# Atmega328.net
KiCad netlist of a schematic drawn in Altium Designer
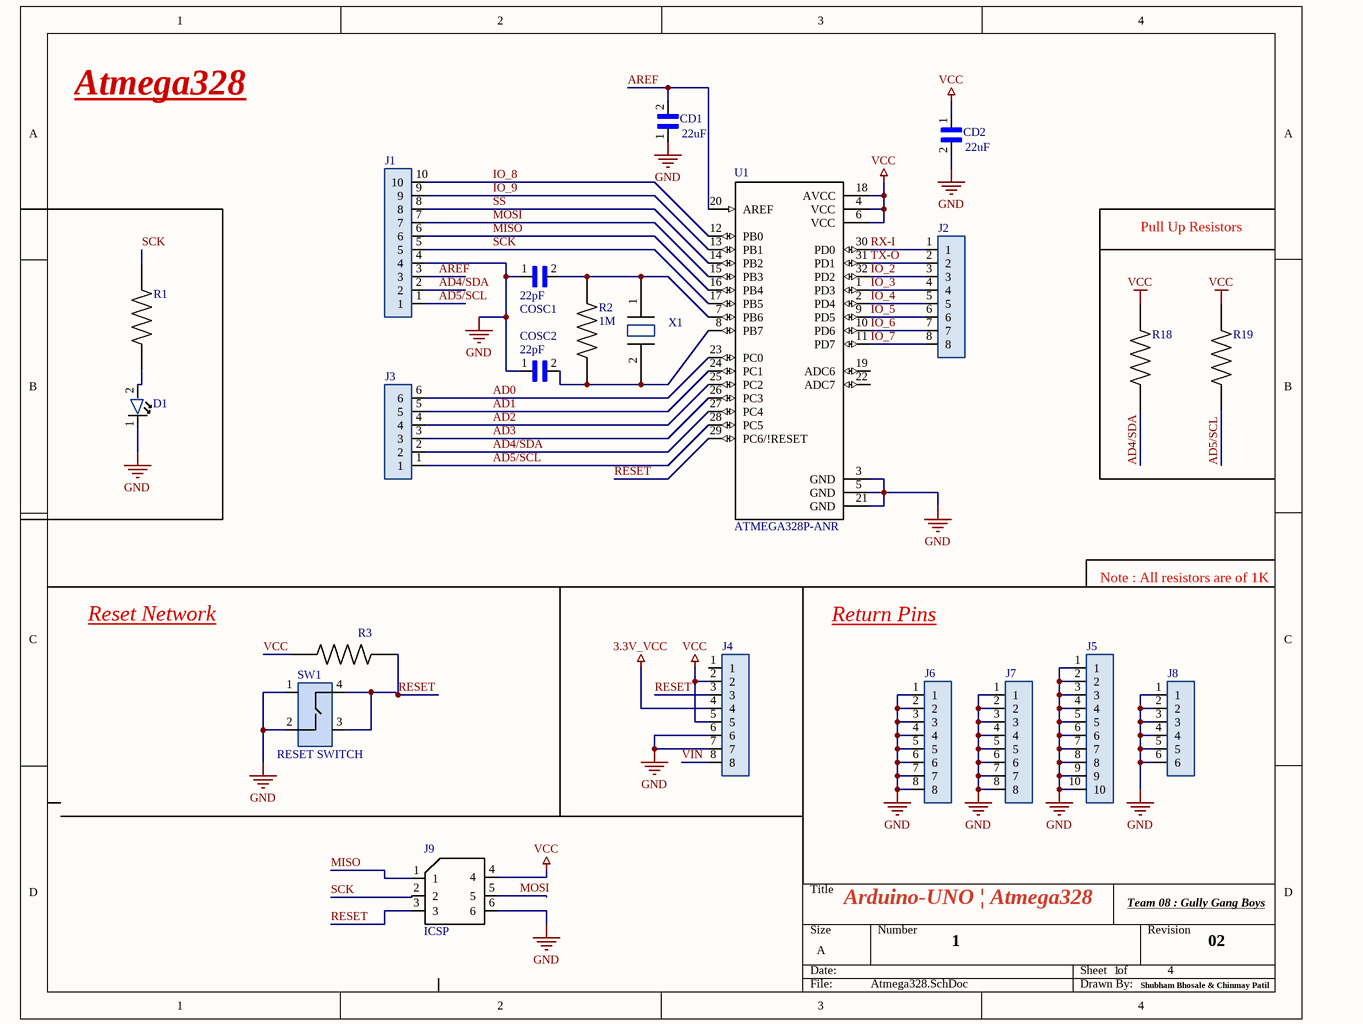
[diagram p0: Atmega328.SchDoc]

(export (version "E")
  (design (tool "Eeschema 10.0.6"))
  (components
    (comp (ref "CD1")
      (value "22uF")
      (footprint "1206_Passive")
      (description "22µF ±20% 16V Ceramic Capacitor X5R 1206 (3216 Metric)")
      (fields (field (name "DIGIKEY PART") "1276-2728-1-ND"))
      (libsource (lib "brd2_rev2") (part "1206_22uF"))
    )
    (comp (ref "CD2")
      (value "22uF")
      (footprint "1206_Passive")
      (description "22µF ±20% 16V Ceramic Capacitor X5R 1206 (3216 Metric)")
      (fields (field (name "DIGIKEY PART") "1276-2728-1-ND"))
      (libsource (lib "brd2_rev2") (part "1206_22uF"))
    )
    (comp (ref "COSC1")
      (value "22pF")
      (footprint "1206_Passive")
      (description "22pF ±5% 16V Ceramic Capacitor C0G, NP0 1206 (3216 Metric)")
      (fields (field (name "DIGIKEY PART") "732-7867-1-ND"))
      (libsource (lib "brd2_rev2") (part "1206_22pF"))
    )
    (comp (ref "COSC2")
      (value "22pF")
      (footprint "1206_Passive")
      (description "22pF ±5% 16V Ceramic Capacitor C0G, NP0 1206 (3216 Metric)")
      (fields (field (name "DIGIKEY PART") "732-7867-1-ND"))
      (libsource (lib "brd2_rev2") (part "1206_22pF"))
    )
    (comp (ref "D1")
      (value "LTST-C150CKT")
      (footprint "LED")
      (description "Red 638nm LED Indication - Discrete 1.8V 1206 (3216 Metric)")
      (fields (field (name "DIGIKEY PART") "160-1167-1-ND"))
      (libsource (lib "brd2_rev2") (part "1206_RED_LED"))
    )
    (comp (ref "J1")
      (value "PPTC101LFBN-RC")
      (footprint "10_PIN")
      (description "10 Position Header Connector 0.100\" (2.54mm) Through Hole Tin")
      (fields (field (name "DIGIKEY PART") "S7008-ND"))
      (libsource (lib "brd2_rev2") (part "10_PIN_FEMALE"))
    )
    (comp (ref "J2")
      (value "PPTC081LFBN-RC")
      (footprint "8_PIN")
      (description "8 Position Header Connector 0.100\" (2.54mm) Through Hole Tin")
      (fields (field (name "DIGIKEY PART") "S7006-ND"))
      (libsource (lib "brd2_rev2") (part "8_PIN_FEMALE"))
    )
    (comp (ref "J3")
      (value "PPTC061LFBN-RC")
      (footprint "6_PIN")
      (description "6 Position Header Connector 0.100\" (2.54mm) Through Hole Tin")
      (fields (field (name "DIGIKEY PART") "S7004-ND"))
      (libsource (lib "") (part "6_PIN_FEMALE_1"))
    )
    (comp (ref "J4")
      (value "PPTC081LFBN-RC")
      (footprint "8_PIN")
      (description "8 Position Header Connector 0.100\" (2.54mm) Through Hole Tin")
      (fields (field (name "DIGIKEY PART") "S7006-ND"))
      (libsource (lib "brd2_rev2") (part "8_PIN_FEMALE"))
    )
    (comp (ref "J5")
      (value "PPTC101LFBN-RC")
      (footprint "10_PIN")
      (description "10 Position Header Connector 0.100\" (2.54mm) Through Hole Tin")
      (fields (field (name "DIGIKEY PART") "S7008-ND"))
      (libsource (lib "") (part "10_PIN_FEMALE_1"))
    )
    (comp (ref "J6")
      (value "PPTC081LFBN-RC")
      (footprint "8_PIN")
      (description "8 Position Header Connector 0.100\" (2.54mm) Through Hole Tin")
      (fields (field (name "DIGIKEY PART") "S7006-ND"))
      (libsource (lib "brd2_rev2") (part "8_PIN_FEMALE"))
    )
    (comp (ref "J7")
      (value "PPTC081LFBN-RC")
      (footprint "8_PIN")
      (description "8 Position Header Connector 0.100\" (2.54mm) Through Hole Tin")
      (fields (field (name "DIGIKEY PART") "S7006-ND"))
      (libsource (lib "brd2_rev2") (part "8_PIN_FEMALE"))
    )
    (comp (ref "J8")
      (value "PPTC061LFBN-RC")
      (footprint "6_PIN")
      (description "6 Position Header Connector 0.100\" (2.54mm) Through Hole Tin")
      (fields (field (name "DIGIKEY PART") "S7004-ND"))
      (libsource (lib "brd2_rev2") (part "6_PIN_FEMALE"))
    )
    (comp (ref "J9")
      (value "ICSP")
      (footprint "ICSP")
      (description "Connector Header Through Hole 6 position 0.079\" (2.00mm)")
      (fields (field (name "DIGIKEY PART") "S5801-03-ND"))
      (libsource (lib "brd2_rev2") (part "ICSP"))
    )
    (comp (ref "R1")
      (value "RNCP1206FTD1K00")
      (footprint "1206_Passive")
      (description "1 kOhms ±1% 0.5W, 1/2W Chip Resistor 1206 (3216 Metric) Anti-Sulfur, Moisture Resistant Thin Film")
      (fields (field (name "DIGIKEY PART") "RNCP1206FTD1K00CT-ND"))
      (libsource (lib "brd2_rev2") (part "1206_1K"))
    )
    (comp (ref "R2")
      (value "1M")
      (footprint "1206_Passive")
      (description "1 MOhms ±5% 0.25W, 1/4W Chip Resistor 1206 (3216 Metric) Automotive AEC-Q200 Thick Film")
      (fields (field (name "DIGIKEY PART") "Number RMCF1206JT1M00CT-ND"))
      (libsource (lib "brd2_rev2") (part "1206_1M"))
    )
    (comp (ref "R3")
      (value "RNCP1206FTD1K00")
      (footprint "1206_Passive")
      (description "1 kOhms ±1% 0.5W, 1/2W Chip Resistor 1206 (3216 Metric) Anti-Sulfur, Moisture Resistant Thin Film")
      (fields (field (name "DIGIKEY PART") "RNCP1206FTD1K00CT-ND"))
      (libsource (lib "brd2_rev2") (part "1206_1K"))
    )
    (comp (ref "R18")
      (value "RNCP1206FTD1K00")
      (footprint "1206_Passive")
      (description "1 kOhms ±1% 0.5W, 1/2W Chip Resistor 1206 (3216 Metric) Anti-Sulfur, Moisture Resistant Thin Film")
      (fields (field (name "DIGIKEY PART") "RNCP1206FTD1K00CT-ND"))
      (libsource (lib "brd2_rev2") (part "1206_1K"))
    )
    (comp (ref "R19")
      (value "RNCP1206FTD1K00")
      (footprint "1206_Passive")
      (description "1 kOhms ±1% 0.5W, 1/2W Chip Resistor 1206 (3216 Metric) Anti-Sulfur, Moisture Resistant Thin Film")
      (fields (field (name "DIGIKEY PART") "RNCP1206FTD1K00CT-ND"))
      (libsource (lib "brd2_rev2") (part "1206_1K"))
    )
    (comp (ref "SW1")
      (value "RESET SWITCH")
      (footprint "Switch")
      (description "Tactile Switch SPST-NO Top Actuated Surface Mount")
      (fields (field (name "DIGIKEY PART") "EG5350CT-ND"))
      (libsource (lib "brd2_rev2") (part "Push_Button"))
    )
    (comp (ref "U1")
      (value "ATMEGA328P-ANR")
      (footprint "ATMega328P")
      (description "AVR AVR® ATmega Microcontroller IC 8-Bit 20MHz 32KB (16K x 16) FLASH 32-TQFP (7x7)")
      (fields (field (name "DIGIKEY PART") "ATMEGA328P-ANRCT-ND"))
      (libsource (lib "brd2_rev2") (part "ATMega328P"))
    )
    (comp (ref "X1")
      (value "ABLS-16.000MHZ-B4-T")
      (footprint "Crystal")
      (description "16MHz ±30ppm Crystal 18pF 40 Ohms HC-49/US")
      (fields (field (name "DIGIKEY PART") "535-10226-1-ND"))
      (libsource (lib "brd2_rev2") (part "16MHz_Crystal"))
    )
  )
  (nets
    (net (code "1") (name "/AD0") (class "Default")
      (node (ref "J3") (pin "6") (pinfunction "6_6") (pintype "passive"))
      (node (ref "U1") (pin "23") (pinfunction "PC0_23") (pintype "bidirectional"))
    )
    (net (code "2") (name "/AD1") (class "Default")
      (node (ref "J3") (pin "5") (pinfunction "5_5") (pintype "passive"))
      (node (ref "U1") (pin "24") (pinfunction "PC1_24") (pintype "bidirectional"))
    )
    (net (code "3") (name "/AD2") (class "Default")
      (node (ref "J3") (pin "4") (pinfunction "4_4") (pintype "passive"))
      (node (ref "U1") (pin "25") (pinfunction "PC2_25") (pintype "bidirectional"))
    )
    (net (code "4") (name "/AD3") (class "Default")
      (node (ref "J3") (pin "3") (pinfunction "3_3") (pintype "passive"))
      (node (ref "U1") (pin "26") (pinfunction "PC3_26") (pintype "bidirectional"))
    )
    (net (code "5") (name "/AD4{slash}SDA") (class "Default")
      (node (ref "J1") (pin "2") (pinfunction "2_2") (pintype "passive"))
      (node (ref "J3") (pin "2") (pinfunction "2_2") (pintype "passive"))
      (node (ref "R18") (pin "1") (pinfunction "1_1") (pintype "passive"))
      (node (ref "U1") (pin "27") (pinfunction "PC4_27") (pintype "bidirectional"))
    )
    (net (code "6") (name "/AD5{slash}SCL") (class "Default")
      (node (ref "J1") (pin "1") (pinfunction "1_1") (pintype "passive"))
      (node (ref "J3") (pin "1") (pinfunction "1_1") (pintype "passive"))
      (node (ref "R19") (pin "1") (pinfunction "1_1") (pintype "passive"))
      (node (ref "U1") (pin "28") (pinfunction "PC5_28") (pintype "bidirectional"))
    )
    (net (code "7") (name "/AREF") (class "Default")
      (node (ref "CD1") (pin "2") (pinfunction "2_2") (pintype "passive"))
      (node (ref "J1") (pin "3") (pinfunction "3_3") (pintype "passive"))
      (node (ref "U1") (pin "20") (pinfunction "AREF_20") (pintype "input"))
    )
    (net (code "8") (name "/IO_2") (class "Default")
      (node (ref "J2") (pin "3") (pinfunction "3_3") (pintype "passive"))
      (node (ref "U1") (pin "32") (pinfunction "PD2_32") (pintype "bidirectional"))
    )
    (net (code "9") (name "/IO_3") (class "Default")
      (node (ref "J2") (pin "4") (pinfunction "4_4") (pintype "passive"))
      (node (ref "U1") (pin "1") (pinfunction "PD3_1") (pintype "bidirectional"))
    )
    (net (code "10") (name "/IO_4") (class "Default")
      (node (ref "J2") (pin "5") (pinfunction "5_5") (pintype "passive"))
      (node (ref "U1") (pin "2") (pinfunction "PD4_2") (pintype "bidirectional"))
    )
    (net (code "11") (name "/IO_5") (class "Default")
      (node (ref "J2") (pin "6") (pinfunction "6_6") (pintype "passive"))
      (node (ref "U1") (pin "9") (pinfunction "PD5_9") (pintype "bidirectional"))
    )
    (net (code "12") (name "/IO_6") (class "Default")
      (node (ref "J2") (pin "7") (pinfunction "7_7") (pintype "passive"))
      (node (ref "U1") (pin "10") (pinfunction "PD6_10") (pintype "bidirectional"))
    )
    (net (code "13") (name "/IO_7") (class "Default")
      (node (ref "J2") (pin "8") (pinfunction "8_8") (pintype "passive"))
      (node (ref "U1") (pin "11") (pinfunction "PD7_11") (pintype "bidirectional"))
    )
    (net (code "14") (name "/IO_8") (class "Default")
      (node (ref "J1") (pin "10") (pinfunction "10_10") (pintype "passive"))
      (node (ref "U1") (pin "12") (pinfunction "PB0_12") (pintype "bidirectional"))
    )
    (net (code "15") (name "/IO_9") (class "Default")
      (node (ref "J1") (pin "9") (pinfunction "9_9") (pintype "passive"))
      (node (ref "U1") (pin "13") (pinfunction "PB1_13") (pintype "bidirectional"))
    )
    (net (code "16") (name "/MISO") (class "Default")
      (node (ref "J1") (pin "6") (pinfunction "6_6") (pintype "passive"))
      (node (ref "J9") (pin "1") (pinfunction "1_1") (pintype "passive"))
      (node (ref "U1") (pin "16") (pinfunction "PB4_16") (pintype "bidirectional"))
    )
    (net (code "17") (name "/MOSI") (class "Default")
      (node (ref "J1") (pin "7") (pinfunction "7_7") (pintype "passive"))
      (node (ref "J9") (pin "5") (pinfunction "5_5") (pintype "passive"))
      (node (ref "U1") (pin "15") (pinfunction "PB3_15") (pintype "bidirectional"))
    )
    (net (code "18") (name "/RESET") (class "Default")
      (node (ref "J4") (pin "3") (pinfunction "3_3") (pintype "passive"))
      (node (ref "J9") (pin "3") (pinfunction "3_3") (pintype "passive"))
      (node (ref "R3") (pin "2") (pinfunction "2_2") (pintype "passive"))
      (node (ref "SW1") (pin "3") (pinfunction "3_3") (pintype "passive"))
      (node (ref "SW1") (pin "4") (pinfunction "4_4") (pintype "passive"))
      (node (ref "U1") (pin "29") (pinfunction "PC6/!RESET_29") (pintype "bidirectional"))
    )
    (net (code "19") (name "/RX-I") (class "Default")
      (node (ref "J2") (pin "1") (pinfunction "1_1") (pintype "passive"))
      (node (ref "U1") (pin "30") (pinfunction "PD0_30") (pintype "bidirectional"))
    )
    (net (code "20") (name "/SCK") (class "Default")
      (node (ref "J1") (pin "5") (pinfunction "5_5") (pintype "passive"))
      (node (ref "J9") (pin "2") (pinfunction "2_2") (pintype "passive"))
      (node (ref "R1") (pin "2") (pinfunction "2_2") (pintype "passive"))
      (node (ref "U1") (pin "17") (pinfunction "PB5_17") (pintype "bidirectional"))
    )
    (net (code "21") (name "/SS") (class "Default")
      (node (ref "J1") (pin "8") (pinfunction "8_8") (pintype "passive"))
      (node (ref "U1") (pin "14") (pinfunction "PB2_14") (pintype "bidirectional"))
    )
    (net (code "22") (name "/TX-O") (class "Default")
      (node (ref "J2") (pin "2") (pinfunction "2_2") (pintype "passive"))
      (node (ref "U1") (pin "31") (pinfunction "PD1_31") (pintype "bidirectional"))
    )
    (net (code "23") (name "/VIN") (class "Default")
      (node (ref "J4") (pin "8") (pinfunction "8_8") (pintype "passive"))
    )
    (net (code "24") (name "3.3V_VCC") (class "Default")
      (node (ref "J4") (pin "4") (pinfunction "4_4") (pintype "passive"))
    )
    (net (code "25") (name "GND") (class "Default")
      (node (ref "CD1") (pin "1") (pinfunction "1_1") (pintype "passive"))
      (node (ref "CD2") (pin "2") (pinfunction "2_2") (pintype "passive"))
      (node (ref "COSC1") (pin "1") (pinfunction "1_1") (pintype "passive"))
      (node (ref "COSC2") (pin "1") (pinfunction "1_1") (pintype "passive"))
      (node (ref "D1") (pin "1") (pinfunction "1_1") (pintype "passive"))
      (node (ref "J1") (pin "4") (pinfunction "4_4") (pintype "passive"))
      (node (ref "J4") (pin "6") (pinfunction "6_6") (pintype "passive"))
      (node (ref "J4") (pin "7") (pinfunction "7_7") (pintype "passive"))
      (node (ref "J5") (pin "1") (pinfunction "1_1") (pintype "passive"))
      (node (ref "J5") (pin "10") (pinfunction "10_10") (pintype "passive"))
      (node (ref "J5") (pin "2") (pinfunction "2_2") (pintype "passive"))
      (node (ref "J5") (pin "3") (pinfunction "3_3") (pintype "passive"))
      (node (ref "J5") (pin "4") (pinfunction "4_4") (pintype "passive"))
      (node (ref "J5") (pin "5") (pinfunction "5_5") (pintype "passive"))
      (node (ref "J5") (pin "6") (pinfunction "6_6") (pintype "passive"))
      (node (ref "J5") (pin "7") (pinfunction "7_7") (pintype "passive"))
      (node (ref "J5") (pin "8") (pinfunction "8_8") (pintype "passive"))
      (node (ref "J5") (pin "9") (pinfunction "9_9") (pintype "passive"))
      (node (ref "J6") (pin "1") (pinfunction "1_1") (pintype "passive"))
      (node (ref "J6") (pin "2") (pinfunction "2_2") (pintype "passive"))
      (node (ref "J6") (pin "3") (pinfunction "3_3") (pintype "passive"))
      (node (ref "J6") (pin "4") (pinfunction "4_4") (pintype "passive"))
      (node (ref "J6") (pin "5") (pinfunction "5_5") (pintype "passive"))
      (node (ref "J6") (pin "6") (pinfunction "6_6") (pintype "passive"))
      (node (ref "J6") (pin "7") (pinfunction "7_7") (pintype "passive"))
      (node (ref "J6") (pin "8") (pinfunction "8_8") (pintype "passive"))
      (node (ref "J7") (pin "1") (pinfunction "1_1") (pintype "passive"))
      (node (ref "J7") (pin "2") (pinfunction "2_2") (pintype "passive"))
      (node (ref "J7") (pin "3") (pinfunction "3_3") (pintype "passive"))
      (node (ref "J7") (pin "4") (pinfunction "4_4") (pintype "passive"))
      (node (ref "J7") (pin "5") (pinfunction "5_5") (pintype "passive"))
      (node (ref "J7") (pin "6") (pinfunction "6_6") (pintype "passive"))
      (node (ref "J7") (pin "7") (pinfunction "7_7") (pintype "passive"))
      (node (ref "J7") (pin "8") (pinfunction "8_8") (pintype "passive"))
      (node (ref "J8") (pin "1") (pinfunction "1_1") (pintype "passive"))
      (node (ref "J8") (pin "2") (pinfunction "2_2") (pintype "passive"))
      (node (ref "J8") (pin "3") (pinfunction "3_3") (pintype "passive"))
      (node (ref "J8") (pin "4") (pinfunction "4_4") (pintype "passive"))
      (node (ref "J8") (pin "5") (pinfunction "5_5") (pintype "passive"))
      (node (ref "J8") (pin "6") (pinfunction "6_6") (pintype "passive"))
      (node (ref "J9") (pin "6") (pinfunction "6_6") (pintype "passive"))
      (node (ref "SW1") (pin "1") (pinfunction "1_1") (pintype "passive"))
      (node (ref "SW1") (pin "2") (pinfunction "2_2") (pintype "passive"))
      (node (ref "U1") (pin "21") (pinfunction "GND_21") (pintype "power_in"))
      (node (ref "U1") (pin "3") (pinfunction "GND_3") (pintype "power_in"))
      (node (ref "U1") (pin "5") (pinfunction "GND_5") (pintype "power_in"))
    )
    (net (code "26") (name "Net-(D1-Pad2)") (class "Default")
      (node (ref "D1") (pin "2") (pinfunction "2_2") (pintype "passive"))
      (node (ref "R1") (pin "1") (pinfunction "1_1") (pintype "passive"))
    )
    (net (code "27") (name "Net-(U1-PB6)") (class "Default")
      (node (ref "COSC1") (pin "2") (pinfunction "2_2") (pintype "passive"))
      (node (ref "R2") (pin "2") (pinfunction "2_2") (pintype "passive"))
      (node (ref "U1") (pin "7") (pinfunction "PB6_7") (pintype "bidirectional"))
      (node (ref "X1") (pin "1") (pinfunction "1_1") (pintype "passive"))
    )
    (net (code "28") (name "Net-(U1-PB7)") (class "Default")
      (node (ref "COSC2") (pin "2") (pinfunction "2_2") (pintype "passive"))
      (node (ref "R2") (pin "1") (pinfunction "1_1") (pintype "passive"))
      (node (ref "U1") (pin "8") (pinfunction "PB7_8") (pintype "bidirectional"))
      (node (ref "X1") (pin "2") (pinfunction "2_2") (pintype "passive"))
    )
    (net (code "29") (name "VCC") (class "Default")
      (node (ref "CD2") (pin "1") (pinfunction "1_1") (pintype "passive"))
      (node (ref "J4") (pin "2") (pinfunction "2_2") (pintype "passive"))
      (node (ref "J4") (pin "5") (pinfunction "5_5") (pintype "passive"))
      (node (ref "J9") (pin "4") (pinfunction "4_4") (pintype "passive"))
      (node (ref "R18") (pin "2") (pinfunction "2_2") (pintype "passive"))
      (node (ref "R19") (pin "2") (pinfunction "2_2") (pintype "passive"))
      (node (ref "R3") (pin "1") (pinfunction "1_1") (pintype "passive"))
      (node (ref "U1") (pin "18") (pinfunction "AVCC_18") (pintype "power_in"))
      (node (ref "U1") (pin "4") (pinfunction "VCC_4") (pintype "power_in"))
      (node (ref "U1") (pin "6") (pinfunction "VCC_6") (pintype "power_in"))
    )
    (net (code "30") (name "unconnected-(J4-Pad1)") (class "Default")
      (node (ref "J4") (pin "1") (pinfunction "1_1") (pintype "passive"))
    )
    (net (code "31") (name "unconnected-(U1-ADC6-Pad19)") (class "Default")
      (node (ref "U1") (pin "19") (pinfunction "ADC6_19") (pintype "bidirectional"))
    )
    (net (code "32") (name "unconnected-(U1-ADC7-Pad22)") (class "Default")
      (node (ref "U1") (pin "22") (pinfunction "ADC7_22") (pintype "bidirectional"))
    )
  )
)
